# LED_Panel.net
KiCad netlist of a schematic drawn in EAGLE
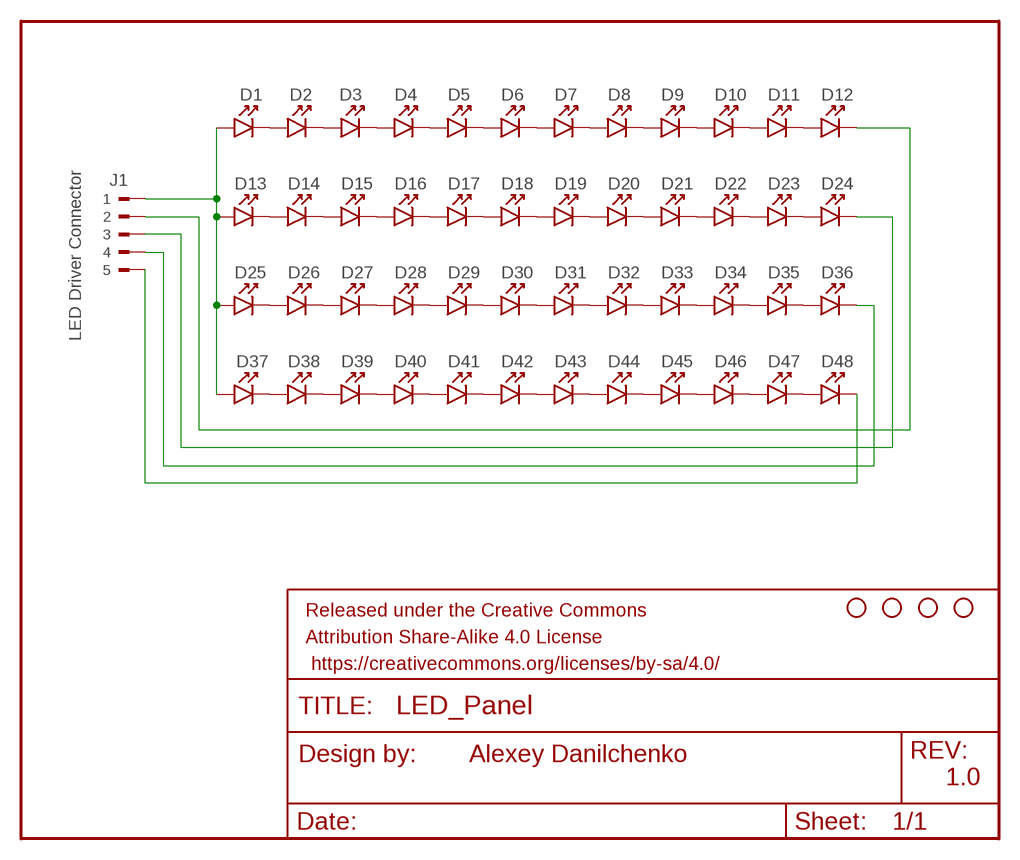
[diagram p0: schematic, sheet 1]

(export (version "E")
  (design (tool "Eeschema 10.0.6"))
  (components
    (comp (ref "D1")
      (value "YUJI_D50")
      (footprint "eagle-import:YUJI_D50")
      (libsource (lib "eagle-import") (part "YUJI_D50"))
    )
    (comp (ref "D2")
      (value "YUJI_D50")
      (footprint "eagle-import:YUJI_D50")
      (libsource (lib "eagle-import") (part "YUJI_D50"))
    )
    (comp (ref "D3")
      (value "YUJI_D50")
      (footprint "eagle-import:YUJI_D50")
      (libsource (lib "eagle-import") (part "YUJI_D50"))
    )
    (comp (ref "D4")
      (value "YUJI_D50")
      (footprint "eagle-import:YUJI_D50")
      (libsource (lib "eagle-import") (part "YUJI_D50"))
    )
    (comp (ref "D5")
      (value "YUJI_D50")
      (footprint "eagle-import:YUJI_D50")
      (libsource (lib "eagle-import") (part "YUJI_D50"))
    )
    (comp (ref "D6")
      (value "YUJI_D50")
      (footprint "eagle-import:YUJI_D50")
      (libsource (lib "eagle-import") (part "YUJI_D50"))
    )
    (comp (ref "D7")
      (value "YUJI_D50")
      (footprint "eagle-import:YUJI_D50")
      (libsource (lib "eagle-import") (part "YUJI_D50"))
    )
    (comp (ref "D8")
      (value "YUJI_D50")
      (footprint "eagle-import:YUJI_D50")
      (libsource (lib "eagle-import") (part "YUJI_D50"))
    )
    (comp (ref "D9")
      (value "YUJI_D50")
      (footprint "eagle-import:YUJI_D50")
      (libsource (lib "eagle-import") (part "YUJI_D50"))
    )
    (comp (ref "D10")
      (value "YUJI_D50")
      (footprint "eagle-import:YUJI_D50")
      (libsource (lib "eagle-import") (part "YUJI_D50"))
    )
    (comp (ref "D11")
      (value "YUJI_D50")
      (footprint "eagle-import:YUJI_D50")
      (libsource (lib "eagle-import") (part "YUJI_D50"))
    )
    (comp (ref "D12")
      (value "YUJI_D50")
      (footprint "eagle-import:YUJI_D50")
      (libsource (lib "eagle-import") (part "YUJI_D50"))
    )
    (comp (ref "D13")
      (value "YUJI_D50")
      (footprint "eagle-import:YUJI_D50")
      (libsource (lib "eagle-import") (part "YUJI_D50"))
    )
    (comp (ref "D14")
      (value "YUJI_D50")
      (footprint "eagle-import:YUJI_D50")
      (libsource (lib "eagle-import") (part "YUJI_D50"))
    )
    (comp (ref "D15")
      (value "YUJI_D50")
      (footprint "eagle-import:YUJI_D50")
      (libsource (lib "eagle-import") (part "YUJI_D50"))
    )
    (comp (ref "D16")
      (value "YUJI_D50")
      (footprint "eagle-import:YUJI_D50")
      (libsource (lib "eagle-import") (part "YUJI_D50"))
    )
    (comp (ref "D17")
      (value "YUJI_D50")
      (footprint "eagle-import:YUJI_D50")
      (libsource (lib "eagle-import") (part "YUJI_D50"))
    )
    (comp (ref "D18")
      (value "YUJI_D50")
      (footprint "eagle-import:YUJI_D50")
      (libsource (lib "eagle-import") (part "YUJI_D50"))
    )
    (comp (ref "D19")
      (value "YUJI_D50")
      (footprint "eagle-import:YUJI_D50")
      (libsource (lib "eagle-import") (part "YUJI_D50"))
    )
    (comp (ref "D20")
      (value "YUJI_D50")
      (footprint "eagle-import:YUJI_D50")
      (libsource (lib "eagle-import") (part "YUJI_D50"))
    )
    (comp (ref "D21")
      (value "YUJI_D50")
      (footprint "eagle-import:YUJI_D50")
      (libsource (lib "eagle-import") (part "YUJI_D50"))
    )
    (comp (ref "D22")
      (value "YUJI_D50")
      (footprint "eagle-import:YUJI_D50")
      (libsource (lib "eagle-import") (part "YUJI_D50"))
    )
    (comp (ref "D23")
      (value "YUJI_D50")
      (footprint "eagle-import:YUJI_D50")
      (libsource (lib "eagle-import") (part "YUJI_D50"))
    )
    (comp (ref "D24")
      (value "YUJI_D50")
      (footprint "eagle-import:YUJI_D50")
      (libsource (lib "eagle-import") (part "YUJI_D50"))
    )
    (comp (ref "D25")
      (value "YUJI_D50")
      (footprint "eagle-import:YUJI_D50")
      (libsource (lib "eagle-import") (part "YUJI_D50"))
    )
    (comp (ref "D26")
      (value "YUJI_D50")
      (footprint "eagle-import:YUJI_D50")
      (libsource (lib "eagle-import") (part "YUJI_D50"))
    )
    (comp (ref "D27")
      (value "YUJI_D50")
      (footprint "eagle-import:YUJI_D50")
      (libsource (lib "eagle-import") (part "YUJI_D50"))
    )
    (comp (ref "D28")
      (value "YUJI_D50")
      (footprint "eagle-import:YUJI_D50")
      (libsource (lib "eagle-import") (part "YUJI_D50"))
    )
    (comp (ref "D29")
      (value "YUJI_D50")
      (footprint "eagle-import:YUJI_D50")
      (libsource (lib "eagle-import") (part "YUJI_D50"))
    )
    (comp (ref "D30")
      (value "YUJI_D50")
      (footprint "eagle-import:YUJI_D50")
      (libsource (lib "eagle-import") (part "YUJI_D50"))
    )
    (comp (ref "D31")
      (value "YUJI_D50")
      (footprint "eagle-import:YUJI_D50")
      (libsource (lib "eagle-import") (part "YUJI_D50"))
    )
    (comp (ref "D32")
      (value "YUJI_D50")
      (footprint "eagle-import:YUJI_D50")
      (libsource (lib "eagle-import") (part "YUJI_D50"))
    )
    (comp (ref "D33")
      (value "YUJI_D50")
      (footprint "eagle-import:YUJI_D50")
      (libsource (lib "eagle-import") (part "YUJI_D50"))
    )
    (comp (ref "D34")
      (value "YUJI_D50")
      (footprint "eagle-import:YUJI_D50")
      (libsource (lib "eagle-import") (part "YUJI_D50"))
    )
    (comp (ref "D35")
      (value "YUJI_D50")
      (footprint "eagle-import:YUJI_D50")
      (libsource (lib "eagle-import") (part "YUJI_D50"))
    )
    (comp (ref "D36")
      (value "YUJI_D50")
      (footprint "eagle-import:YUJI_D50")
      (libsource (lib "eagle-import") (part "YUJI_D50"))
    )
    (comp (ref "D37")
      (value "YUJI_D50")
      (footprint "eagle-import:YUJI_D50")
      (libsource (lib "eagle-import") (part "YUJI_D50"))
    )
    (comp (ref "D38")
      (value "YUJI_D50")
      (footprint "eagle-import:YUJI_D50")
      (libsource (lib "eagle-import") (part "YUJI_D50"))
    )
    (comp (ref "D39")
      (value "YUJI_D50")
      (footprint "eagle-import:YUJI_D50")
      (libsource (lib "eagle-import") (part "YUJI_D50"))
    )
    (comp (ref "D40")
      (value "YUJI_D50")
      (footprint "eagle-import:YUJI_D50")
      (libsource (lib "eagle-import") (part "YUJI_D50"))
    )
    (comp (ref "D41")
      (value "YUJI_D50")
      (footprint "eagle-import:YUJI_D50")
      (libsource (lib "eagle-import") (part "YUJI_D50"))
    )
    (comp (ref "D42")
      (value "YUJI_D50")
      (footprint "eagle-import:YUJI_D50")
      (libsource (lib "eagle-import") (part "YUJI_D50"))
    )
    (comp (ref "D43")
      (value "YUJI_D50")
      (footprint "eagle-import:YUJI_D50")
      (libsource (lib "eagle-import") (part "YUJI_D50"))
    )
    (comp (ref "D44")
      (value "YUJI_D50")
      (footprint "eagle-import:YUJI_D50")
      (libsource (lib "eagle-import") (part "YUJI_D50"))
    )
    (comp (ref "D45")
      (value "YUJI_D50")
      (footprint "eagle-import:YUJI_D50")
      (libsource (lib "eagle-import") (part "YUJI_D50"))
    )
    (comp (ref "D46")
      (value "YUJI_D50")
      (footprint "eagle-import:YUJI_D50")
      (libsource (lib "eagle-import") (part "YUJI_D50"))
    )
    (comp (ref "D47")
      (value "YUJI_D50")
      (footprint "eagle-import:YUJI_D50")
      (libsource (lib "eagle-import") (part "YUJI_D50"))
    )
    (comp (ref "D48")
      (value "YUJI_D50")
      (footprint "eagle-import:YUJI_D50")
      (libsource (lib "eagle-import") (part "YUJI_D50"))
    )
    (comp (ref "FRAME1")
      (value "FRAME-LEDGER")
      (footprint "eagle-import:CREATIVE_COMMONS")
      (libsource (lib "eagle-import") (part "FRAME-LEDGER"))
    )
    (comp (ref "J1")
      (value "LED Driver Connector")
      (footprint "eagle-import:TERMINAL_BLK_5X5MM")
      (libsource (lib "eagle-import") (part "TERMINAL_BLK_5"))
    )
    (comp (ref "STANDOFF1")
      (value "STAND-OFF")
      (footprint "eagle-import:STAND-OFF")
      (libsource (lib "eagle-import") (part "STAND-OFF"))
    )
    (comp (ref "STANDOFF2")
      (value "STAND-OFF")
      (footprint "eagle-import:STAND-OFF")
      (libsource (lib "eagle-import") (part "STAND-OFF"))
    )
    (comp (ref "STANDOFF3")
      (value "STAND-OFF")
      (footprint "eagle-import:STAND-OFF")
      (libsource (lib "eagle-import") (part "STAND-OFF"))
    )
    (comp (ref "STANDOFF4")
      (value "STAND-OFF")
      (footprint "eagle-import:STAND-OFF")
      (libsource (lib "eagle-import") (part "STAND-OFF"))
    )
  )
  (nets
    (net (code "1") (name "Net-(D1-PadANODE)") (class "Default")
      (node (ref "D1") (pin "ANODE") (pinfunction "ANODE_ANODE") (pintype "bidirectional"))
      (node (ref "D13") (pin "ANODE") (pinfunction "ANODE_ANODE") (pintype "bidirectional"))
      (node (ref "D25") (pin "ANODE") (pinfunction "ANODE_ANODE") (pintype "bidirectional"))
      (node (ref "D37") (pin "ANODE") (pinfunction "ANODE_ANODE") (pintype "bidirectional"))
      (node (ref "J1") (pin "1") (pinfunction "1_1") (pintype "passive"))
    )
    (net (code "2") (name "Net-(D1-PadCATHODE)") (class "Default")
      (node (ref "D1") (pin "CATHODE") (pinfunction "CATHODE_CATHODE") (pintype "bidirectional"))
      (node (ref "D2") (pin "ANODE") (pinfunction "ANODE_ANODE") (pintype "bidirectional"))
    )
    (net (code "3") (name "Net-(D2-PadCATHODE)") (class "Default")
      (node (ref "D2") (pin "CATHODE") (pinfunction "CATHODE_CATHODE") (pintype "bidirectional"))
      (node (ref "D3") (pin "ANODE") (pinfunction "ANODE_ANODE") (pintype "bidirectional"))
    )
    (net (code "4") (name "Net-(D3-PadCATHODE)") (class "Default")
      (node (ref "D3") (pin "CATHODE") (pinfunction "CATHODE_CATHODE") (pintype "bidirectional"))
      (node (ref "D4") (pin "ANODE") (pinfunction "ANODE_ANODE") (pintype "bidirectional"))
    )
    (net (code "5") (name "Net-(D4-PadCATHODE)") (class "Default")
      (node (ref "D4") (pin "CATHODE") (pinfunction "CATHODE_CATHODE") (pintype "bidirectional"))
      (node (ref "D5") (pin "ANODE") (pinfunction "ANODE_ANODE") (pintype "bidirectional"))
    )
    (net (code "6") (name "Net-(D5-PadCATHODE)") (class "Default")
      (node (ref "D5") (pin "CATHODE") (pinfunction "CATHODE_CATHODE") (pintype "bidirectional"))
      (node (ref "D6") (pin "ANODE") (pinfunction "ANODE_ANODE") (pintype "bidirectional"))
    )
    (net (code "7") (name "Net-(D6-PadCATHODE)") (class "Default")
      (node (ref "D6") (pin "CATHODE") (pinfunction "CATHODE_CATHODE") (pintype "bidirectional"))
      (node (ref "D7") (pin "ANODE") (pinfunction "ANODE_ANODE") (pintype "bidirectional"))
    )
    (net (code "8") (name "Net-(D7-PadCATHODE)") (class "Default")
      (node (ref "D7") (pin "CATHODE") (pinfunction "CATHODE_CATHODE") (pintype "bidirectional"))
      (node (ref "D8") (pin "ANODE") (pinfunction "ANODE_ANODE") (pintype "bidirectional"))
    )
    (net (code "9") (name "Net-(D8-PadCATHODE)") (class "Default")
      (node (ref "D8") (pin "CATHODE") (pinfunction "CATHODE_CATHODE") (pintype "bidirectional"))
      (node (ref "D9") (pin "ANODE") (pinfunction "ANODE_ANODE") (pintype "bidirectional"))
    )
    (net (code "10") (name "Net-(D10-PadANODE)") (class "Default")
      (node (ref "D10") (pin "ANODE") (pinfunction "ANODE_ANODE") (pintype "bidirectional"))
      (node (ref "D9") (pin "CATHODE") (pinfunction "CATHODE_CATHODE") (pintype "bidirectional"))
    )
    (net (code "11") (name "Net-(D10-PadCATHODE)") (class "Default")
      (node (ref "D10") (pin "CATHODE") (pinfunction "CATHODE_CATHODE") (pintype "bidirectional"))
      (node (ref "D11") (pin "ANODE") (pinfunction "ANODE_ANODE") (pintype "bidirectional"))
    )
    (net (code "12") (name "Net-(D11-PadCATHODE)") (class "Default")
      (node (ref "D11") (pin "CATHODE") (pinfunction "CATHODE_CATHODE") (pintype "bidirectional"))
      (node (ref "D12") (pin "ANODE") (pinfunction "ANODE_ANODE") (pintype "bidirectional"))
    )
    (net (code "13") (name "Net-(D12-PadCATHODE)") (class "Default")
      (node (ref "D12") (pin "CATHODE") (pinfunction "CATHODE_CATHODE") (pintype "bidirectional"))
      (node (ref "J1") (pin "2") (pinfunction "2_2") (pintype "passive"))
    )
    (net (code "14") (name "Net-(D13-PadCATHODE)") (class "Default")
      (node (ref "D13") (pin "CATHODE") (pinfunction "CATHODE_CATHODE") (pintype "bidirectional"))
      (node (ref "D14") (pin "ANODE") (pinfunction "ANODE_ANODE") (pintype "bidirectional"))
    )
    (net (code "15") (name "Net-(D14-PadCATHODE)") (class "Default")
      (node (ref "D14") (pin "CATHODE") (pinfunction "CATHODE_CATHODE") (pintype "bidirectional"))
      (node (ref "D15") (pin "ANODE") (pinfunction "ANODE_ANODE") (pintype "bidirectional"))
    )
    (net (code "16") (name "Net-(D15-PadCATHODE)") (class "Default")
      (node (ref "D15") (pin "CATHODE") (pinfunction "CATHODE_CATHODE") (pintype "bidirectional"))
      (node (ref "D16") (pin "ANODE") (pinfunction "ANODE_ANODE") (pintype "bidirectional"))
    )
    (net (code "17") (name "Net-(D16-PadCATHODE)") (class "Default")
      (node (ref "D16") (pin "CATHODE") (pinfunction "CATHODE_CATHODE") (pintype "bidirectional"))
      (node (ref "D17") (pin "ANODE") (pinfunction "ANODE_ANODE") (pintype "bidirectional"))
    )
    (net (code "18") (name "Net-(D17-PadCATHODE)") (class "Default")
      (node (ref "D17") (pin "CATHODE") (pinfunction "CATHODE_CATHODE") (pintype "bidirectional"))
      (node (ref "D18") (pin "ANODE") (pinfunction "ANODE_ANODE") (pintype "bidirectional"))
    )
    (net (code "19") (name "Net-(D18-PadCATHODE)") (class "Default")
      (node (ref "D18") (pin "CATHODE") (pinfunction "CATHODE_CATHODE") (pintype "bidirectional"))
      (node (ref "D19") (pin "ANODE") (pinfunction "ANODE_ANODE") (pintype "bidirectional"))
    )
    (net (code "20") (name "Net-(D19-PadCATHODE)") (class "Default")
      (node (ref "D19") (pin "CATHODE") (pinfunction "CATHODE_CATHODE") (pintype "bidirectional"))
      (node (ref "D20") (pin "ANODE") (pinfunction "ANODE_ANODE") (pintype "bidirectional"))
    )
    (net (code "21") (name "Net-(D20-PadCATHODE)") (class "Default")
      (node (ref "D20") (pin "CATHODE") (pinfunction "CATHODE_CATHODE") (pintype "bidirectional"))
      (node (ref "D21") (pin "ANODE") (pinfunction "ANODE_ANODE") (pintype "bidirectional"))
    )
    (net (code "22") (name "Net-(D21-PadCATHODE)") (class "Default")
      (node (ref "D21") (pin "CATHODE") (pinfunction "CATHODE_CATHODE") (pintype "bidirectional"))
      (node (ref "D22") (pin "ANODE") (pinfunction "ANODE_ANODE") (pintype "bidirectional"))
    )
    (net (code "23") (name "Net-(D22-PadCATHODE)") (class "Default")
      (node (ref "D22") (pin "CATHODE") (pinfunction "CATHODE_CATHODE") (pintype "bidirectional"))
      (node (ref "D23") (pin "ANODE") (pinfunction "ANODE_ANODE") (pintype "bidirectional"))
    )
    (net (code "24") (name "Net-(D23-PadCATHODE)") (class "Default")
      (node (ref "D23") (pin "CATHODE") (pinfunction "CATHODE_CATHODE") (pintype "bidirectional"))
      (node (ref "D24") (pin "ANODE") (pinfunction "ANODE_ANODE") (pintype "bidirectional"))
    )
    (net (code "25") (name "Net-(D24-PadCATHODE)") (class "Default")
      (node (ref "D24") (pin "CATHODE") (pinfunction "CATHODE_CATHODE") (pintype "bidirectional"))
      (node (ref "J1") (pin "3") (pinfunction "3_3") (pintype "passive"))
    )
    (net (code "26") (name "Net-(D25-PadCATHODE)") (class "Default")
      (node (ref "D25") (pin "CATHODE") (pinfunction "CATHODE_CATHODE") (pintype "bidirectional"))
      (node (ref "D26") (pin "ANODE") (pinfunction "ANODE_ANODE") (pintype "bidirectional"))
    )
    (net (code "27") (name "Net-(D26-PadCATHODE)") (class "Default")
      (node (ref "D26") (pin "CATHODE") (pinfunction "CATHODE_CATHODE") (pintype "bidirectional"))
      (node (ref "D27") (pin "ANODE") (pinfunction "ANODE_ANODE") (pintype "bidirectional"))
    )
    (net (code "28") (name "Net-(D27-PadCATHODE)") (class "Default")
      (node (ref "D27") (pin "CATHODE") (pinfunction "CATHODE_CATHODE") (pintype "bidirectional"))
      (node (ref "D28") (pin "ANODE") (pinfunction "ANODE_ANODE") (pintype "bidirectional"))
    )
    (net (code "29") (name "Net-(D28-PadCATHODE)") (class "Default")
      (node (ref "D28") (pin "CATHODE") (pinfunction "CATHODE_CATHODE") (pintype "bidirectional"))
      (node (ref "D29") (pin "ANODE") (pinfunction "ANODE_ANODE") (pintype "bidirectional"))
    )
    (net (code "30") (name "Net-(D29-PadCATHODE)") (class "Default")
      (node (ref "D29") (pin "CATHODE") (pinfunction "CATHODE_CATHODE") (pintype "bidirectional"))
      (node (ref "D30") (pin "ANODE") (pinfunction "ANODE_ANODE") (pintype "bidirectional"))
    )
    (net (code "31") (name "Net-(D30-PadCATHODE)") (class "Default")
      (node (ref "D30") (pin "CATHODE") (pinfunction "CATHODE_CATHODE") (pintype "bidirectional"))
      (node (ref "D31") (pin "ANODE") (pinfunction "ANODE_ANODE") (pintype "bidirectional"))
    )
    (net (code "32") (name "Net-(D31-PadCATHODE)") (class "Default")
      (node (ref "D31") (pin "CATHODE") (pinfunction "CATHODE_CATHODE") (pintype "bidirectional"))
      (node (ref "D32") (pin "ANODE") (pinfunction "ANODE_ANODE") (pintype "bidirectional"))
    )
    (net (code "33") (name "Net-(D32-PadCATHODE)") (class "Default")
      (node (ref "D32") (pin "CATHODE") (pinfunction "CATHODE_CATHODE") (pintype "bidirectional"))
      (node (ref "D33") (pin "ANODE") (pinfunction "ANODE_ANODE") (pintype "bidirectional"))
    )
    (net (code "34") (name "Net-(D33-PadCATHODE)") (class "Default")
      (node (ref "D33") (pin "CATHODE") (pinfunction "CATHODE_CATHODE") (pintype "bidirectional"))
      (node (ref "D34") (pin "ANODE") (pinfunction "ANODE_ANODE") (pintype "bidirectional"))
    )
    (net (code "35") (name "Net-(D34-PadCATHODE)") (class "Default")
      (node (ref "D34") (pin "CATHODE") (pinfunction "CATHODE_CATHODE") (pintype "bidirectional"))
      (node (ref "D35") (pin "ANODE") (pinfunction "ANODE_ANODE") (pintype "bidirectional"))
    )
    (net (code "36") (name "Net-(D35-PadCATHODE)") (class "Default")
      (node (ref "D35") (pin "CATHODE") (pinfunction "CATHODE_CATHODE") (pintype "bidirectional"))
      (node (ref "D36") (pin "ANODE") (pinfunction "ANODE_ANODE") (pintype "bidirectional"))
    )
    (net (code "37") (name "Net-(D36-PadCATHODE)") (class "Default")
      (node (ref "D36") (pin "CATHODE") (pinfunction "CATHODE_CATHODE") (pintype "bidirectional"))
      (node (ref "J1") (pin "4") (pinfunction "4_4") (pintype "passive"))
    )
    (net (code "38") (name "Net-(D37-PadCATHODE)") (class "Default")
      (node (ref "D37") (pin "CATHODE") (pinfunction "CATHODE_CATHODE") (pintype "bidirectional"))
      (node (ref "D38") (pin "ANODE") (pinfunction "ANODE_ANODE") (pintype "bidirectional"))
    )
    (net (code "39") (name "Net-(D38-PadCATHODE)") (class "Default")
      (node (ref "D38") (pin "CATHODE") (pinfunction "CATHODE_CATHODE") (pintype "bidirectional"))
      (node (ref "D39") (pin "ANODE") (pinfunction "ANODE_ANODE") (pintype "bidirectional"))
    )
    (net (code "40") (name "Net-(D39-PadCATHODE)") (class "Default")
      (node (ref "D39") (pin "CATHODE") (pinfunction "CATHODE_CATHODE") (pintype "bidirectional"))
      (node (ref "D40") (pin "ANODE") (pinfunction "ANODE_ANODE") (pintype "bidirectional"))
    )
    (net (code "41") (name "Net-(D40-PadCATHODE)") (class "Default")
      (node (ref "D40") (pin "CATHODE") (pinfunction "CATHODE_CATHODE") (pintype "bidirectional"))
      (node (ref "D41") (pin "ANODE") (pinfunction "ANODE_ANODE") (pintype "bidirectional"))
    )
    (net (code "42") (name "Net-(D41-PadCATHODE)") (class "Default")
      (node (ref "D41") (pin "CATHODE") (pinfunction "CATHODE_CATHODE") (pintype "bidirectional"))
      (node (ref "D42") (pin "ANODE") (pinfunction "ANODE_ANODE") (pintype "bidirectional"))
    )
    (net (code "43") (name "Net-(D42-PadCATHODE)") (class "Default")
      (node (ref "D42") (pin "CATHODE") (pinfunction "CATHODE_CATHODE") (pintype "bidirectional"))
      (node (ref "D43") (pin "ANODE") (pinfunction "ANODE_ANODE") (pintype "bidirectional"))
    )
    (net (code "44") (name "Net-(D43-PadCATHODE)") (class "Default")
      (node (ref "D43") (pin "CATHODE") (pinfunction "CATHODE_CATHODE") (pintype "bidirectional"))
      (node (ref "D44") (pin "ANODE") (pinfunction "ANODE_ANODE") (pintype "bidirectional"))
    )
    (net (code "45") (name "Net-(D44-PadCATHODE)") (class "Default")
      (node (ref "D44") (pin "CATHODE") (pinfunction "CATHODE_CATHODE") (pintype "bidirectional"))
      (node (ref "D45") (pin "ANODE") (pinfunction "ANODE_ANODE") (pintype "bidirectional"))
    )
    (net (code "46") (name "Net-(D45-PadCATHODE)") (class "Default")
      (node (ref "D45") (pin "CATHODE") (pinfunction "CATHODE_CATHODE") (pintype "bidirectional"))
      (node (ref "D46") (pin "ANODE") (pinfunction "ANODE_ANODE") (pintype "bidirectional"))
    )
    (net (code "47") (name "Net-(D46-PadCATHODE)") (class "Default")
      (node (ref "D46") (pin "CATHODE") (pinfunction "CATHODE_CATHODE") (pintype "bidirectional"))
      (node (ref "D47") (pin "ANODE") (pinfunction "ANODE_ANODE") (pintype "bidirectional"))
    )
    (net (code "48") (name "Net-(D47-PadCATHODE)") (class "Default")
      (node (ref "D47") (pin "CATHODE") (pinfunction "CATHODE_CATHODE") (pintype "bidirectional"))
      (node (ref "D48") (pin "ANODE") (pinfunction "ANODE_ANODE") (pintype "bidirectional"))
    )
    (net (code "49") (name "Net-(D48-PadCATHODE)") (class "Default")
      (node (ref "D48") (pin "CATHODE") (pinfunction "CATHODE_CATHODE") (pintype "bidirectional"))
      (node (ref "J1") (pin "5") (pinfunction "5_5") (pintype "passive"))
    )
  )
)
